# Reflectance.net
KiCad netlist of a schematic drawn in Altium Designer
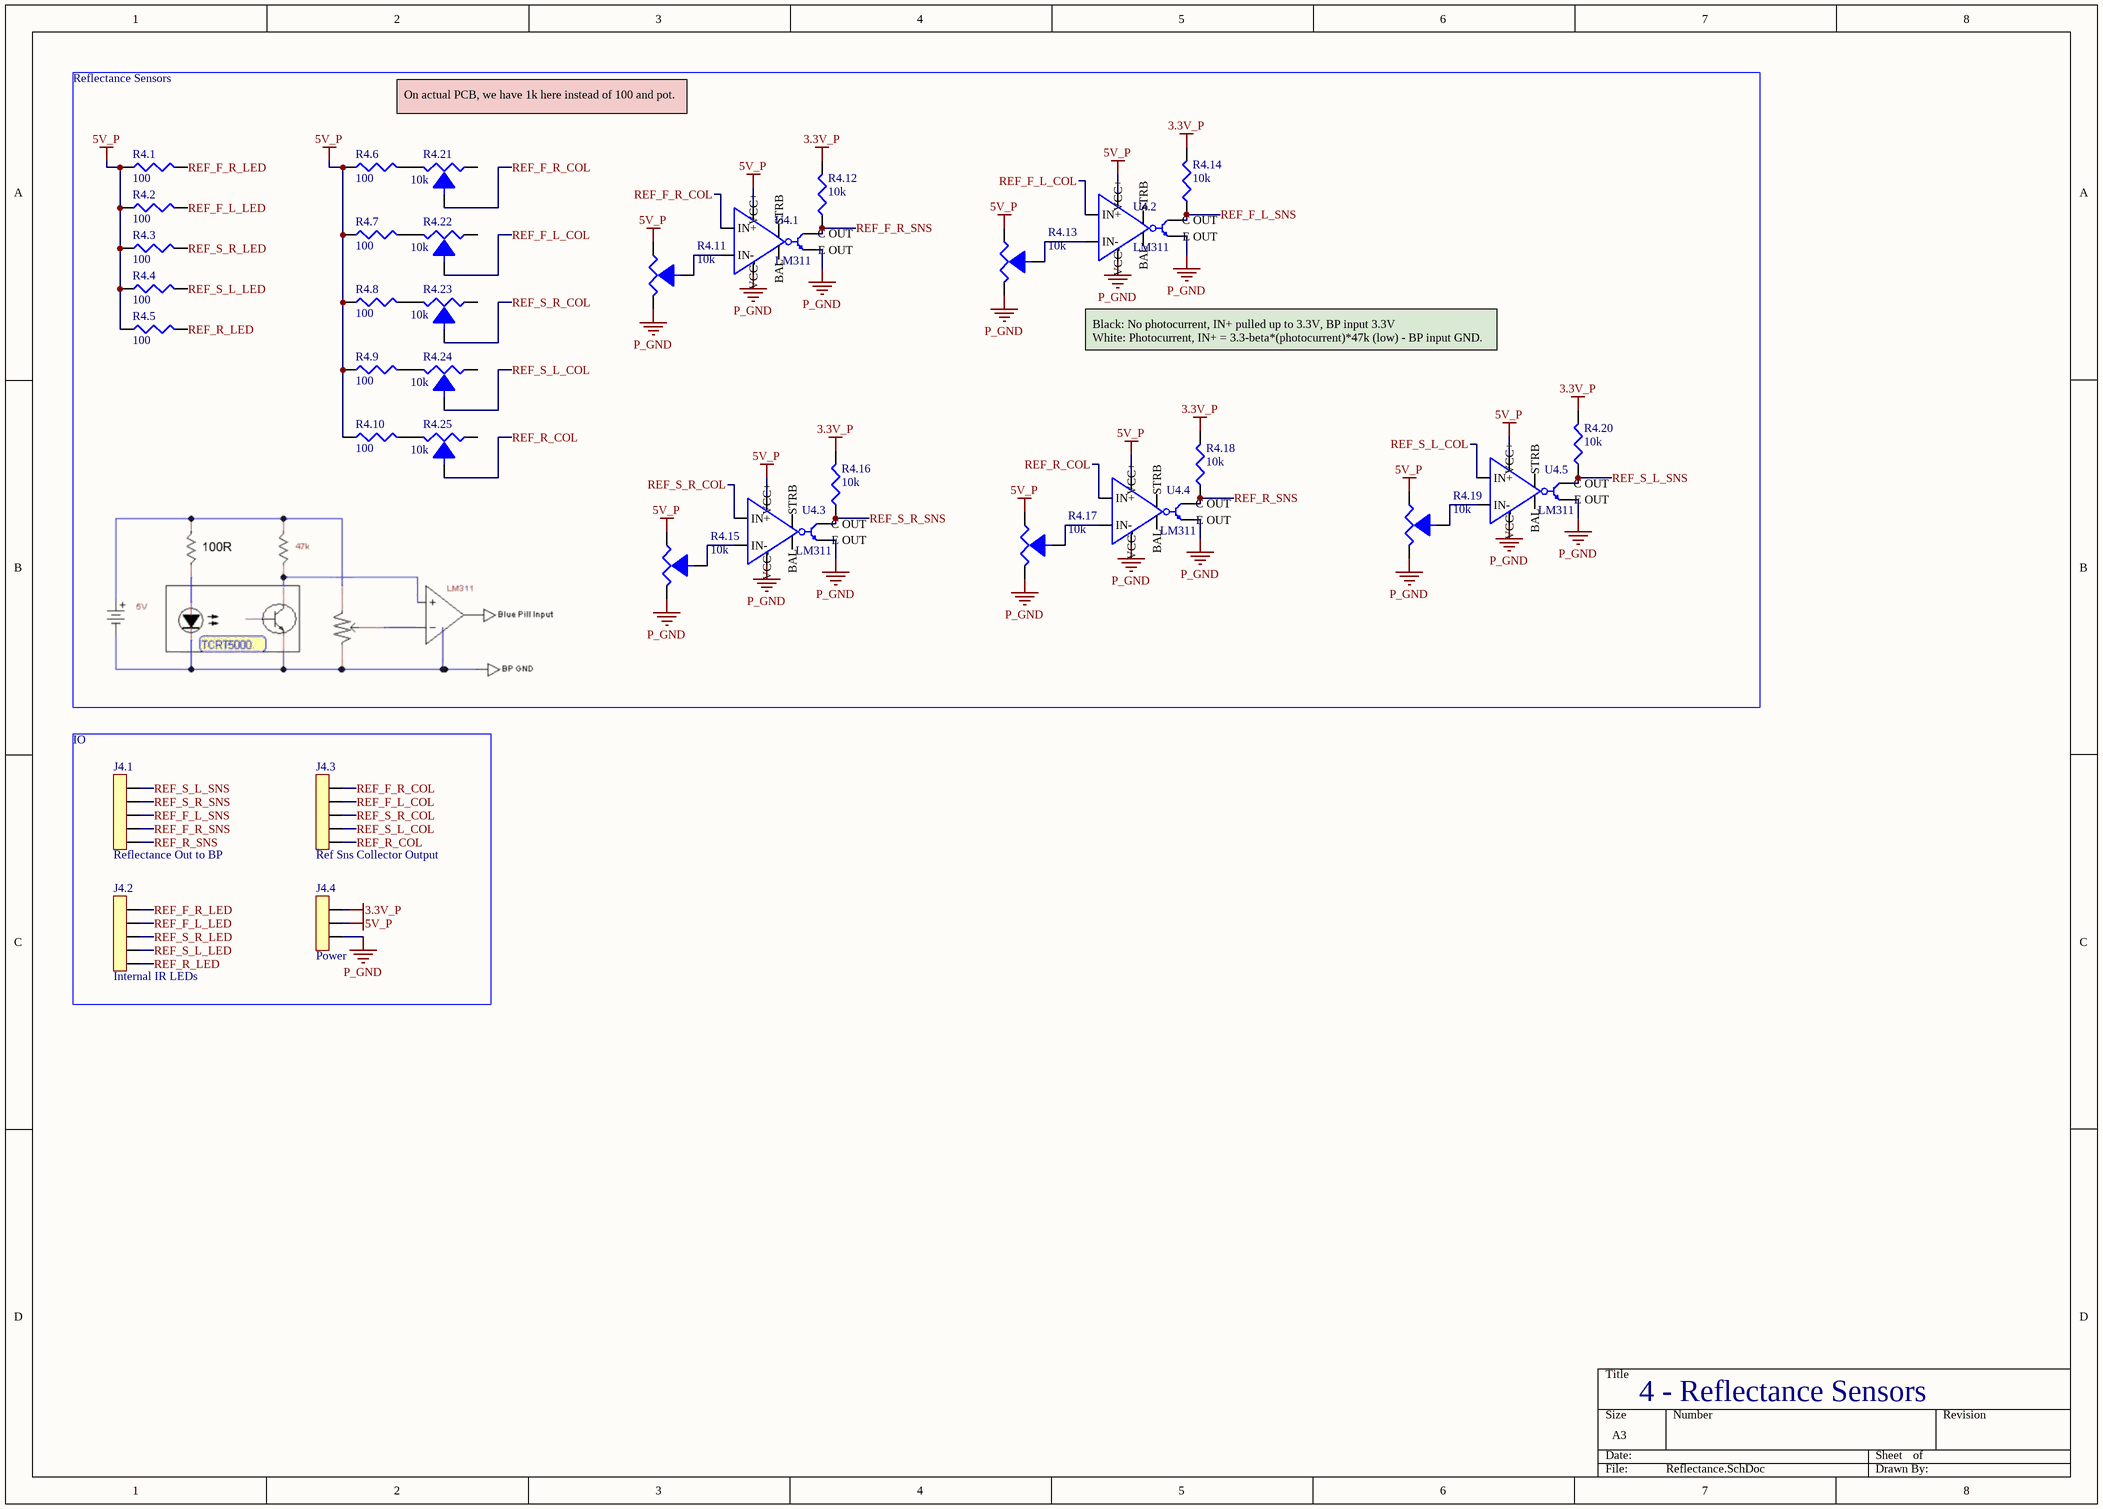
[diagram p0: Reflectance.SchDoc]
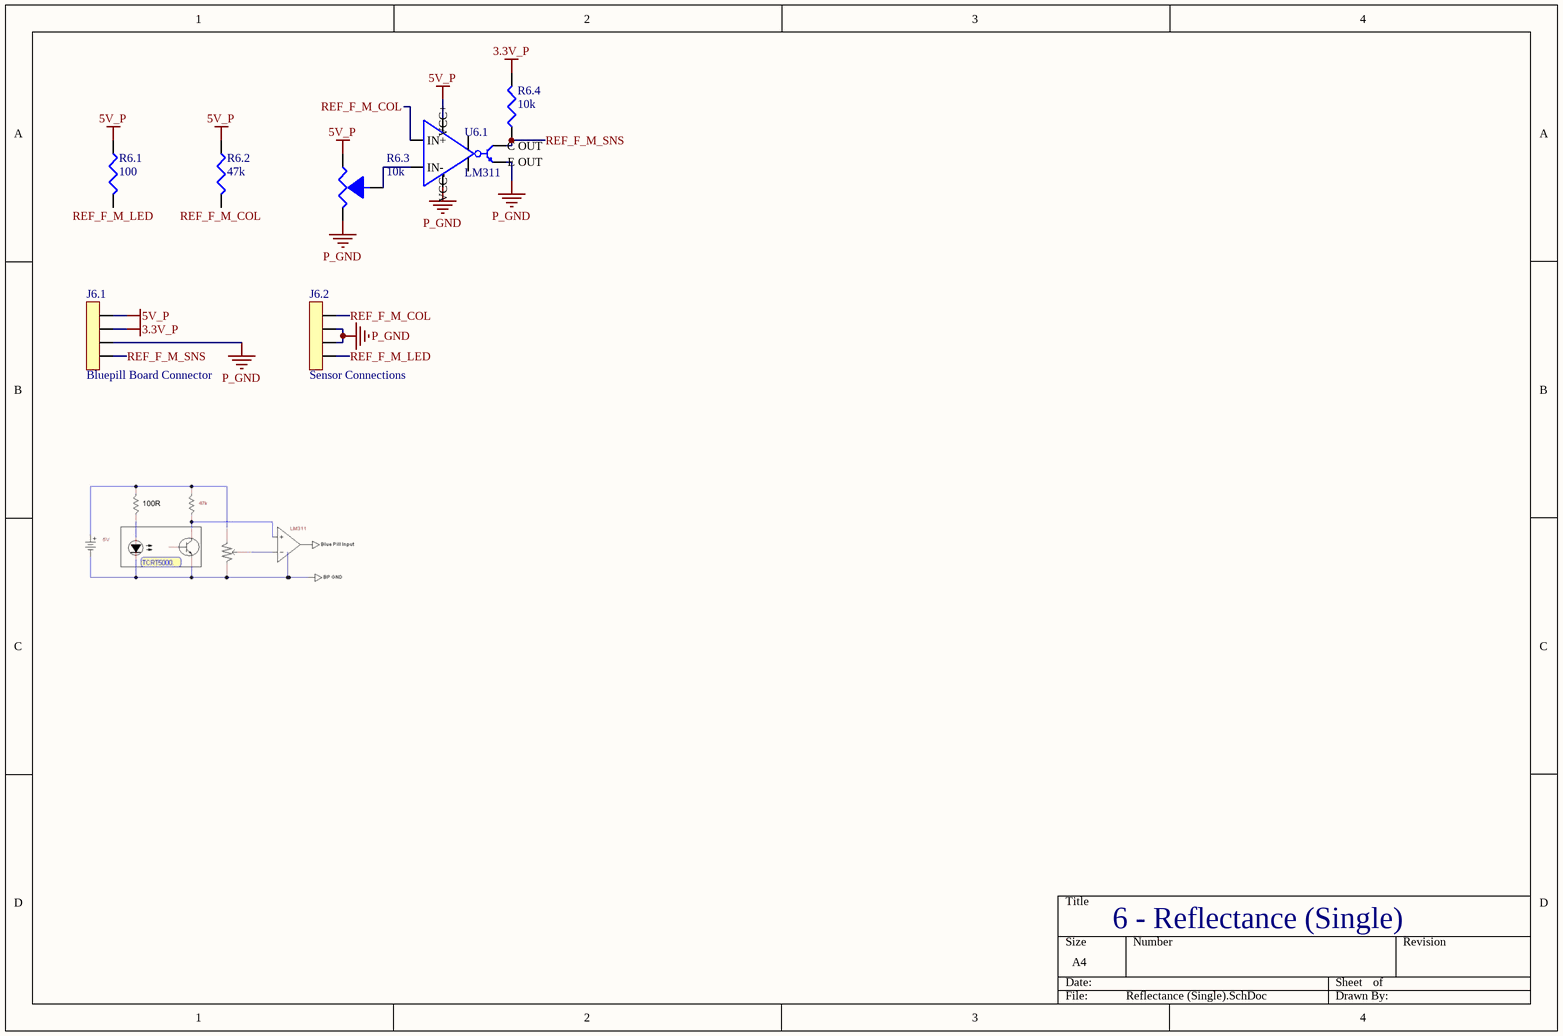
[diagram p1: Reflectance (Single).SchDoc]

(export (version "E")
  (design (tool "Eeschema 10.0.6"))
  (components
    (comp (ref "J6.1")
      (value "Bluepill Board Connector")
      (footprint "4Pos JST")
      (description "4pos Conn")
      (libsource (lib "SPICEBot_SchLib") (part "4pos Conn"))
    )
    (comp (ref "J6.2")
      (value "Sensor Connections")
      (footprint "4Pos JST")
      (description "4pos Conn")
      (libsource (lib "SPICEBot_SchLib") (part "4pos Conn"))
    )
    (comp (ref "R6.1")
      (value "100")
      (footprint "Res_Generic")
      (libsource (lib "SPICEBot_SchLib") (part "Res_Generic"))
    )
    (comp (ref "R6.2")
      (value "47k")
      (footprint "Res_Generic")
      (libsource (lib "SPICEBot_SchLib") (part "Res_Generic"))
    )
    (comp (ref "R6.3")
      (value "10k")
      (footprint "Pot Generic")
      (libsource (lib "SPICEBot_SchLib") (part "Pot_Generic"))
    )
    (comp (ref "R6.4")
      (value "10k")
      (footprint "Res_Generic")
      (libsource (lib "SPICEBot_SchLib") (part "Res_Generic"))
    )
    (comp (ref "U6.1")
      (value "LM311")
      (footprint "DIP8")
      (description "LM311 IC DIFF COMPARATOR STROBE 8-DIP")
      (libsource (lib "SPICEBot_SchLib") (part "LM311 Comparator"))
    )
  )
  (nets
    (net (code "1") (name "/REF_F_M_COL") (class "Default")
      (node (ref "J6.2") (pin "4") (pinfunction "4_4") (pintype "passive"))
      (node (ref "R6.2") (pin "2") (pinfunction "2_2") (pintype "passive"))
      (node (ref "U6.1") (pin "2") (pinfunction "IN+_2") (pintype "passive"))
    )
    (net (code "2") (name "/REF_F_M_LED") (class "Default")
      (node (ref "J6.2") (pin "1") (pinfunction "1_1") (pintype "passive"))
      (node (ref "R6.1") (pin "2") (pinfunction "2_2") (pintype "passive"))
    )
    (net (code "3") (name "/REF_F_M_SNS") (class "Default")
      (node (ref "J6.1") (pin "1") (pinfunction "1_1") (pintype "passive"))
      (node (ref "R6.4") (pin "1") (pinfunction "1_1") (pintype "passive"))
      (node (ref "U6.1") (pin "7") (pinfunction "C_OUT_7") (pintype "passive"))
    )
    (net (code "4") (name "3.3V_P") (class "Default")
      (node (ref "J6.1") (pin "3") (pinfunction "3_3") (pintype "passive"))
      (node (ref "R6.4") (pin "2") (pinfunction "2_2") (pintype "passive"))
    )
    (net (code "5") (name "5V_P") (class "Default")
      (node (ref "J6.1") (pin "4") (pinfunction "4_4") (pintype "passive"))
      (node (ref "R6.1") (pin "1") (pinfunction "1_1") (pintype "passive"))
      (node (ref "R6.2") (pin "1") (pinfunction "1_1") (pintype "passive"))
      (node (ref "R6.3") (pin "3") (pinfunction "3_3") (pintype "passive"))
      (node (ref "U6.1") (pin "8") (pinfunction "VCC+_8") (pintype "passive"))
    )
    (net (code "6") (name "Net-(U6.1-IN-)") (class "Default")
      (node (ref "R6.3") (pin "2") (pinfunction "2_2") (pintype "passive"))
      (node (ref "U6.1") (pin "3") (pinfunction "IN-_3") (pintype "passive"))
    )
    (net (code "7") (name "P_GND") (class "Default")
      (node (ref "J6.1") (pin "2") (pinfunction "2_2") (pintype "passive"))
      (node (ref "J6.2") (pin "2") (pinfunction "2_2") (pintype "passive"))
      (node (ref "J6.2") (pin "3") (pinfunction "3_3") (pintype "passive"))
      (node (ref "R6.3") (pin "1") (pinfunction "1_1") (pintype "passive"))
      (node (ref "U6.1") (pin "1") (pinfunction "E_OUT_1") (pintype "passive"))
      (node (ref "U6.1") (pin "4") (pinfunction "VCC-_4") (pintype "passive"))
    )
    (net (code "8") (name "unconnected-(U6.1-BAL-Pad5)") (class "Default")
      (node (ref "U6.1") (pin "5") (pinfunction "BAL_5") (pintype "passive"))
    )
    (net (code "9") (name "unconnected-(U6.1-STRB-Pad6)") (class "Default")
      (node (ref "U6.1") (pin "6") (pinfunction "STRB_6") (pintype "passive"))
    )
  )
)
